# GBA_VU_Meter_Main_Board_v1_0.net
KiCad netlist of a schematic drawn in EAGLE
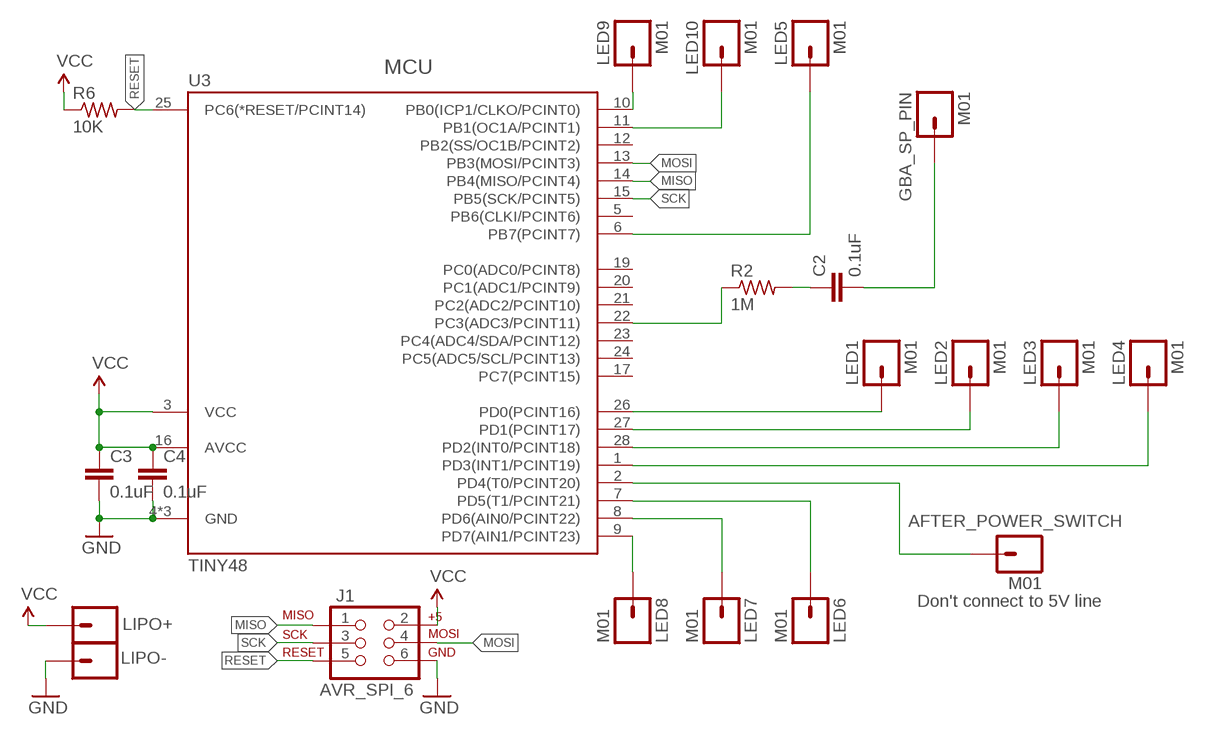
[diagram p0: schematic, sheet 1]

(export (version "E")
  (design (tool "Eeschema 10.0.6"))
  (components
    (comp (ref "AFTER_POWER_SWITCH")
      (value "M01")
      (footprint "eagle-import:1X01_SMD_SM")
      (libsource (lib "eagle-import") (part "M01"))
    )
    (comp (ref "C2")
      (value "0.1uF")
      (footprint "eagle-import:C0603K")
      (libsource (lib "eagle-import") (part "CAP0603"))
    )
    (comp (ref "C3")
      (value "0.1uF")
      (footprint "eagle-import:C0603K")
      (libsource (lib "eagle-import") (part "CAP0603"))
    )
    (comp (ref "C4")
      (value "0.1uF")
      (footprint "eagle-import:C0603K")
      (libsource (lib "eagle-import") (part "CAP0603"))
    )
    (comp (ref "GBA_SP_PIN")
      (value "M01")
      (footprint "eagle-import:1X01_SMD_SM")
      (libsource (lib "eagle-import") (part "M01"))
    )
    (comp (ref "J1")
      (value "AVR_SPI_6")
      (footprint "eagle-import:2X3_2")
      (libsource (lib "eagle-import") (part "AVR_SPI_PRG_6"))
    )
    (comp (ref "LED1")
      (value "M01")
      (footprint "eagle-import:1X01_SMD_SM")
      (libsource (lib "eagle-import") (part "M01"))
    )
    (comp (ref "LED2")
      (value "M01")
      (footprint "eagle-import:1X01_SMD_SM")
      (libsource (lib "eagle-import") (part "M01"))
    )
    (comp (ref "LED3")
      (value "M01")
      (footprint "eagle-import:1X01_SMD_SM")
      (libsource (lib "eagle-import") (part "M01"))
    )
    (comp (ref "LED4")
      (value "M01")
      (footprint "eagle-import:1X01_SMD_SM")
      (libsource (lib "eagle-import") (part "M01"))
    )
    (comp (ref "LED5")
      (value "M01")
      (footprint "eagle-import:1X01_SMD_SM")
      (libsource (lib "eagle-import") (part "M01"))
    )
    (comp (ref "LED6")
      (value "M01")
      (footprint "eagle-import:1X01_SMD_SM")
      (libsource (lib "eagle-import") (part "M01"))
    )
    (comp (ref "LED7")
      (value "M01")
      (footprint "eagle-import:1X01_SMD_SM")
      (libsource (lib "eagle-import") (part "M01"))
    )
    (comp (ref "LED8")
      (value "M01")
      (footprint "eagle-import:1X01_SMD_SM")
      (libsource (lib "eagle-import") (part "M01"))
    )
    (comp (ref "LED9")
      (value "M01")
      (footprint "eagle-import:1X01_SMD_SM")
      (libsource (lib "eagle-import") (part "M01"))
    )
    (comp (ref "LED10")
      (value "M01")
      (footprint "eagle-import:1X01_SMD_SM")
      (libsource (lib "eagle-import") (part "M01"))
    )
    (comp (ref "LIPO+")
      (value "M01SMALL")
      (footprint "eagle-import:1X01_SMD_SMALL")
      (libsource (lib "eagle-import") (part "M01SMALL"))
    )
    (comp (ref "LIPO-")
      (value "M01SMALL")
      (footprint "eagle-import:1X01_SMD_SMALL")
      (libsource (lib "eagle-import") (part "M01SMALL"))
    )
    (comp (ref "R2")
      (value "1M")
      (footprint "eagle-import:R0603_S")
      (libsource (lib "eagle-import") (part "R-US_R0603_S"))
    )
    (comp (ref "R6")
      (value "10K")
      (footprint "eagle-import:R0603_S")
      (libsource (lib "eagle-import") (part "R-US_R0603_S"))
    )
    (comp (ref "U3")
      (value "TINY48")
      (footprint "eagle-import:VQFN-28")
      (libsource (lib "eagle-import") (part "TINY48"))
    )
  )
  (nets
    (net (code "1") (name "GND") (class "Default")
      (node (ref "C3") (pin "2") (pinfunction "2_2") (pintype "passive"))
      (node (ref "C4") (pin "2") (pinfunction "2_2") (pintype "passive"))
      (node (ref "J1") (pin "6") (pinfunction "6_6") (pintype "passive"))
      (node (ref "LIPO-") (pin "1") (pinfunction "1_1") (pintype "passive"))
      (node (ref "U3") (pin "18") (pinfunction "GND_18") (pintype "power_in"))
      (node (ref "U3") (pin "29") (pinfunction "GND_29") (pintype "power_in"))
      (node (ref "U3") (pin "4") (pinfunction "GND_4") (pintype "power_in"))
    )
    (net (code "2") (name "MISO") (class "Default")
      (node (ref "J1") (pin "1") (pinfunction "1_1") (pintype "passive"))
      (node (ref "U3") (pin "14") (pinfunction "PB4(MISO/PCINT4)_14") (pintype "bidirectional"))
    )
    (net (code "3") (name "MOSI") (class "Default")
      (node (ref "J1") (pin "4") (pinfunction "4_4") (pintype "passive"))
      (node (ref "U3") (pin "13") (pinfunction "PB3(MOSI/PCINT3)_13") (pintype "bidirectional"))
    )
    (net (code "4") (name "Net-(AFTER_POWER_SWITCH-1)") (class "Default")
      (node (ref "AFTER_POWER_SWITCH") (pin "P$1") (pinfunction "1_P$1") (pintype "passive"))
      (node (ref "U3") (pin "2") (pinfunction "PD4(T0/PCINT20)_2") (pintype "bidirectional"))
    )
    (net (code "5") (name "Net-(C2-Pad1)") (class "Default")
      (node (ref "C2") (pin "1") (pinfunction "1_1") (pintype "passive"))
      (node (ref "R2") (pin "2") (pinfunction "2_2") (pintype "passive"))
    )
    (net (code "6") (name "Net-(GBA_SP_PIN-1)") (class "Default")
      (node (ref "C2") (pin "2") (pinfunction "2_2") (pintype "passive"))
      (node (ref "GBA_SP_PIN") (pin "P$1") (pinfunction "1_P$1") (pintype "passive"))
    )
    (net (code "7") (name "Net-(LED1-1)") (class "Default")
      (node (ref "LED1") (pin "P$1") (pinfunction "1_P$1") (pintype "passive"))
      (node (ref "U3") (pin "26") (pinfunction "PD0(PCINT16)_26") (pintype "bidirectional"))
    )
    (net (code "8") (name "Net-(LED2-1)") (class "Default")
      (node (ref "LED2") (pin "P$1") (pinfunction "1_P$1") (pintype "passive"))
      (node (ref "U3") (pin "27") (pinfunction "PD1(PCINT17)_27") (pintype "bidirectional"))
    )
    (net (code "9") (name "Net-(LED3-1)") (class "Default")
      (node (ref "LED3") (pin "P$1") (pinfunction "1_P$1") (pintype "passive"))
      (node (ref "U3") (pin "28") (pinfunction "PD2(INT0/PCINT18)_28") (pintype "bidirectional"))
    )
    (net (code "10") (name "Net-(LED4-1)") (class "Default")
      (node (ref "LED4") (pin "P$1") (pinfunction "1_P$1") (pintype "passive"))
      (node (ref "U3") (pin "1") (pinfunction "PD3(INT1/PCINT19)_1") (pintype "bidirectional"))
    )
    (net (code "11") (name "Net-(LED5-1)") (class "Default")
      (node (ref "LED5") (pin "P$1") (pinfunction "1_P$1") (pintype "passive"))
      (node (ref "U3") (pin "6") (pinfunction "PB7(PCINT7)_6") (pintype "bidirectional"))
    )
    (net (code "12") (name "Net-(LED6-1)") (class "Default")
      (node (ref "LED6") (pin "P$1") (pinfunction "1_P$1") (pintype "passive"))
      (node (ref "U3") (pin "7") (pinfunction "PD5(T1/PCINT21)_7") (pintype "bidirectional"))
    )
    (net (code "13") (name "Net-(LED7-1)") (class "Default")
      (node (ref "LED7") (pin "P$1") (pinfunction "1_P$1") (pintype "passive"))
      (node (ref "U3") (pin "8") (pinfunction "PD6(AIN0/PCINT22)_8") (pintype "bidirectional"))
    )
    (net (code "14") (name "Net-(LED8-1)") (class "Default")
      (node (ref "LED8") (pin "P$1") (pinfunction "1_P$1") (pintype "passive"))
      (node (ref "U3") (pin "9") (pinfunction "PD7(AIN1/PCINT23)_9") (pintype "bidirectional"))
    )
    (net (code "15") (name "Net-(LED9-1)") (class "Default")
      (node (ref "LED9") (pin "P$1") (pinfunction "1_P$1") (pintype "passive"))
      (node (ref "U3") (pin "10") (pinfunction "PB0(ICP1/CLKO/PCINT0)_10") (pintype "bidirectional"))
    )
    (net (code "16") (name "Net-(LED10-1)") (class "Default")
      (node (ref "LED10") (pin "P$1") (pinfunction "1_P$1") (pintype "passive"))
      (node (ref "U3") (pin "11") (pinfunction "PB1(OC1A/PCINT1)_11") (pintype "bidirectional"))
    )
    (net (code "17") (name "Net-(U3-PC3(ADC3{slash}PCINT11))") (class "Default")
      (node (ref "R2") (pin "1") (pinfunction "1_1") (pintype "passive"))
      (node (ref "U3") (pin "22") (pinfunction "PC3(ADC3/PCINT11)_22") (pintype "bidirectional"))
    )
    (net (code "18") (name "RESET") (class "Default")
      (node (ref "J1") (pin "5") (pinfunction "5_5") (pintype "passive"))
      (node (ref "R6") (pin "2") (pinfunction "2_2") (pintype "passive"))
      (node (ref "U3") (pin "25") (pinfunction "PC6(*RESET/PCINT14)_25") (pintype "bidirectional"))
    )
    (net (code "19") (name "SCK") (class "Default")
      (node (ref "J1") (pin "3") (pinfunction "3_3") (pintype "passive"))
      (node (ref "U3") (pin "15") (pinfunction "PB5(SCK/PCINT5)_15") (pintype "bidirectional"))
    )
    (net (code "20") (name "VCC") (class "Default")
      (node (ref "C3") (pin "1") (pinfunction "1_1") (pintype "passive"))
      (node (ref "C4") (pin "1") (pinfunction "1_1") (pintype "passive"))
      (node (ref "J1") (pin "2") (pinfunction "2_2") (pintype "passive"))
      (node (ref "LIPO+") (pin "1") (pinfunction "1_1") (pintype "passive"))
      (node (ref "R6") (pin "1") (pinfunction "1_1") (pintype "passive"))
      (node (ref "U3") (pin "16") (pinfunction "AVCC_16") (pintype "power_in"))
      (node (ref "U3") (pin "3") (pinfunction "VCC_3") (pintype "power_in"))
    )
    (net (code "21") (name "unconnected-(U3-PB2(SS{slash}OC1B{slash}PCINT2)-Pad12)") (class "Default")
      (node (ref "U3") (pin "12") (pinfunction "PB2(SS/OC1B/PCINT2)_12") (pintype "bidirectional"))
    )
    (net (code "22") (name "unconnected-(U3-PB6(CLKI{slash}PCINT6)-Pad5)") (class "Default")
      (node (ref "U3") (pin "5") (pinfunction "PB6(CLKI/PCINT6)_5") (pintype "bidirectional"))
    )
    (net (code "23") (name "unconnected-(U3-PC0(ADC0{slash}PCINT8)-Pad19)") (class "Default")
      (node (ref "U3") (pin "19") (pinfunction "PC0(ADC0/PCINT8)_19") (pintype "bidirectional"))
    )
    (net (code "24") (name "unconnected-(U3-PC1(ADC1{slash}PCINT9)-Pad20)") (class "Default")
      (node (ref "U3") (pin "20") (pinfunction "PC1(ADC1/PCINT9)_20") (pintype "bidirectional"))
    )
    (net (code "25") (name "unconnected-(U3-PC2(ADC2{slash}PCINT10)-Pad21)") (class "Default")
      (node (ref "U3") (pin "21") (pinfunction "PC2(ADC2/PCINT10)_21") (pintype "bidirectional"))
    )
    (net (code "26") (name "unconnected-(U3-PC4(ADC4{slash}SDA{slash}PCINT12)-Pad23)") (class "Default")
      (node (ref "U3") (pin "23") (pinfunction "PC4(ADC4/SDA/PCINT12)_23") (pintype "bidirectional"))
    )
    (net (code "27") (name "unconnected-(U3-PC5(ADC5{slash}SCL{slash}PCINT13)-Pad24)") (class "Default")
      (node (ref "U3") (pin "24") (pinfunction "PC5(ADC5/SCL/PCINT13)_24") (pintype "bidirectional"))
    )
    (net (code "28") (name "unconnected-(U3-PC7(PCINT15)-Pad17)") (class "Default")
      (node (ref "U3") (pin "17") (pinfunction "PC7(PCINT15)_17") (pintype "bidirectional"))
    )
  )
)
